# yawc.net
KiCad netlist of a schematic drawn in EAGLE
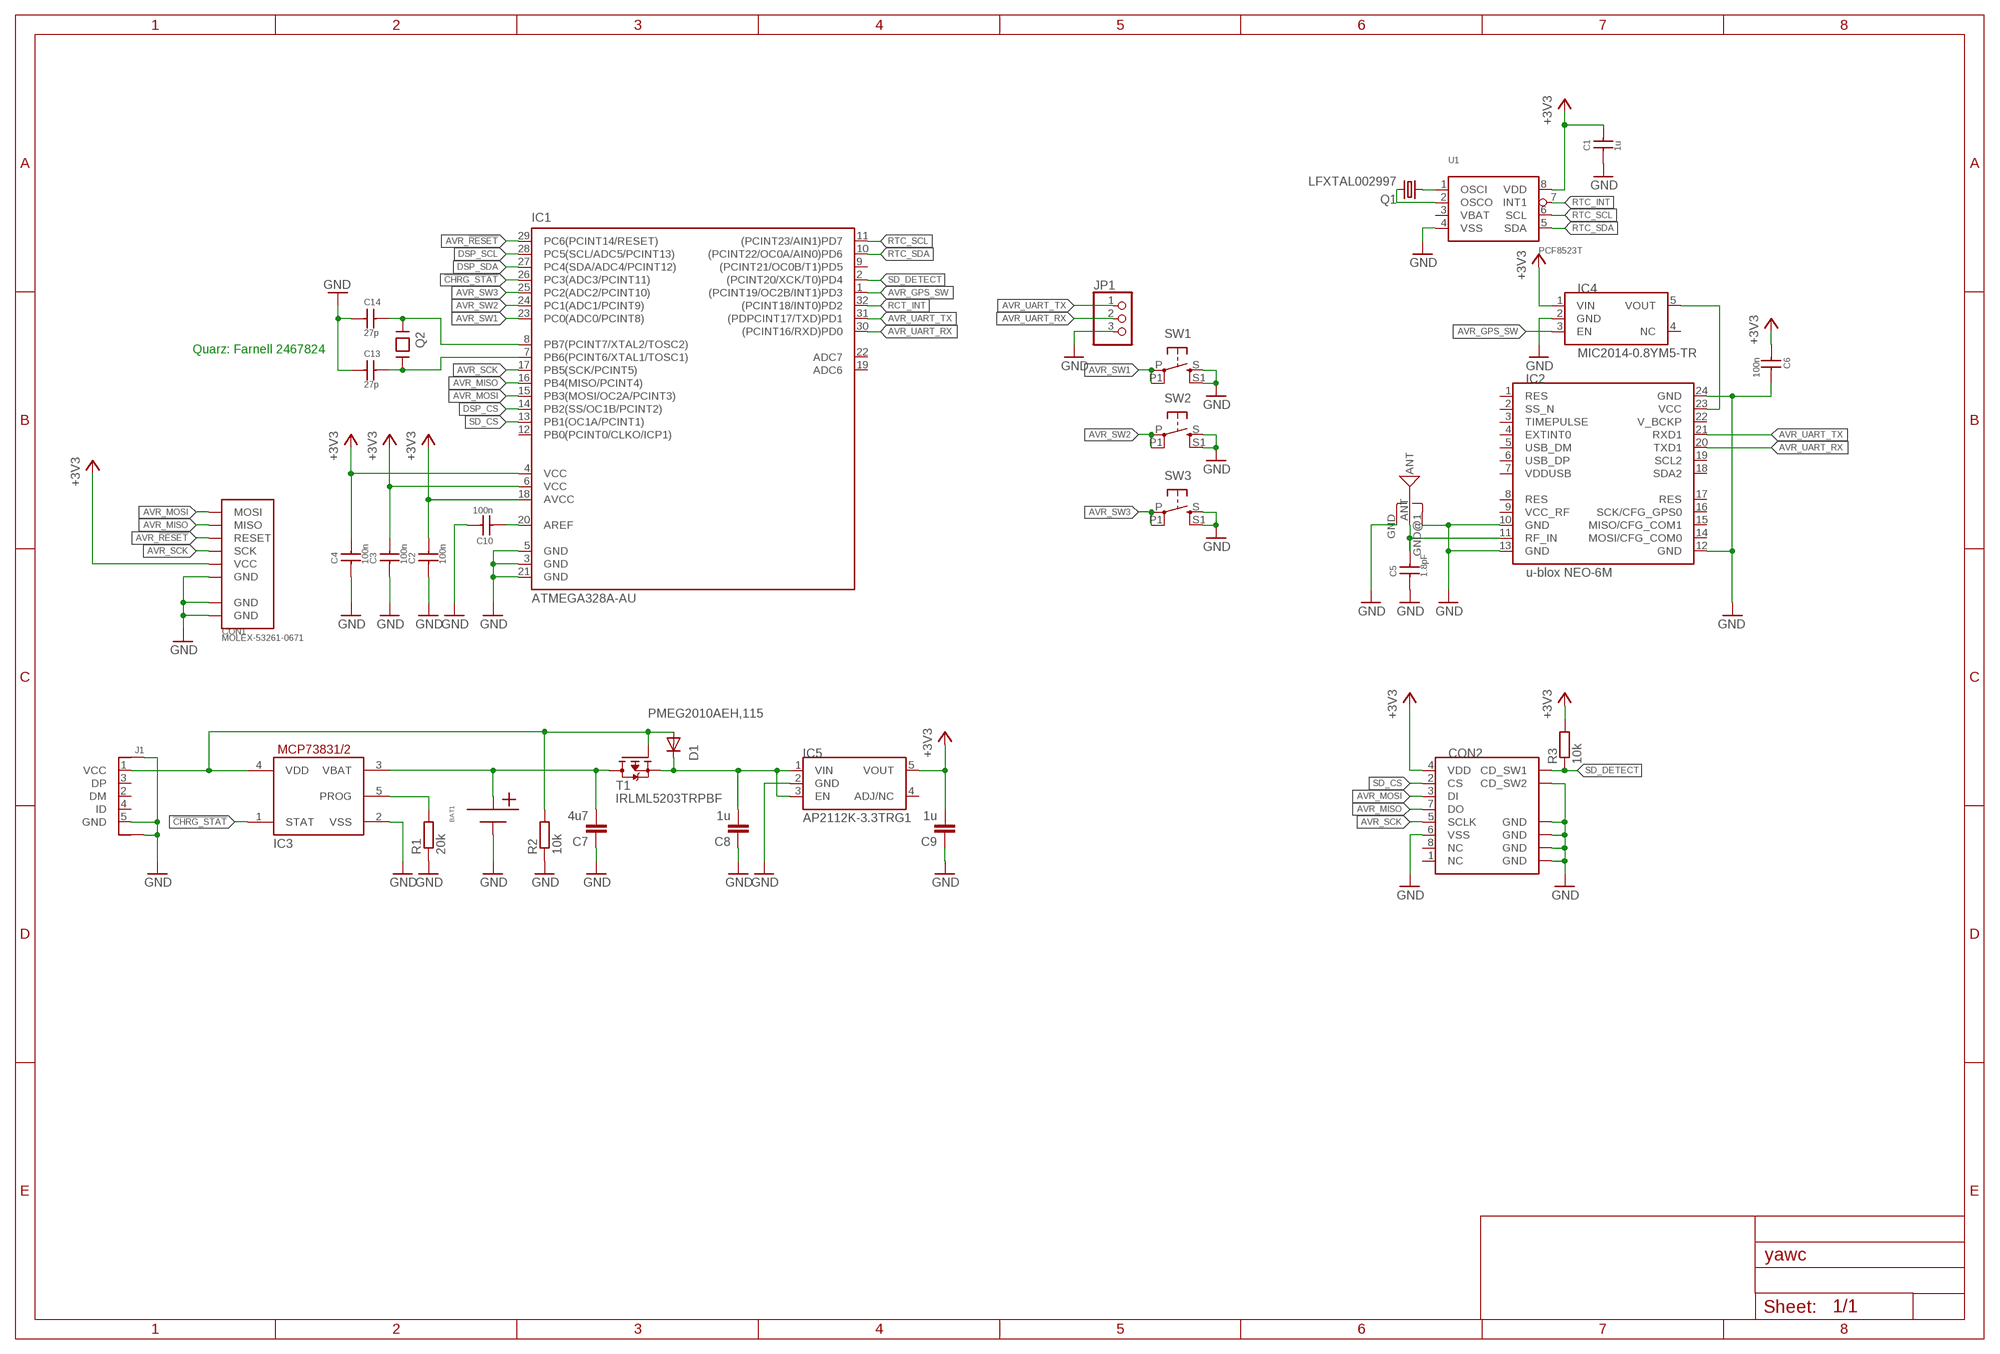
[diagram p0: schematic, sheet 1]

(export (version "E")
  (design (tool "Eeschema 10.0.6"))
  (components
    (comp (ref "BAT1")
      (value "LIPO_1S")
      (footprint "eagle-import:LIPO_1S_SOLDER_CON")
      (libsource (lib "eagle-import") (part "LIPO_1S"))
    )
    (comp (ref "C1")
      (value "1u")
      (footprint "eagle-import:C0603")
      (libsource (lib "eagle-import") (part "C_SMD0603"))
    )
    (comp (ref "C2")
      (value "100n")
      (footprint "eagle-import:C0603")
      (libsource (lib "eagle-import") (part "C_SMD0603"))
    )
    (comp (ref "C3")
      (value "100n")
      (footprint "eagle-import:C0603")
      (libsource (lib "eagle-import") (part "C_SMD0603"))
    )
    (comp (ref "C4")
      (value "100n")
      (footprint "eagle-import:C0603")
      (libsource (lib "eagle-import") (part "C_SMD0603"))
    )
    (comp (ref "C5")
      (value "1.8pF")
      (footprint "eagle-import:C0603")
      (libsource (lib "eagle-import") (part "C_SMD0603"))
    )
    (comp (ref "C6")
      (value "100n")
      (footprint "eagle-import:C0603")
      (libsource (lib "eagle-import") (part "C_SMD0603"))
    )
    (comp (ref "C7")
      (value "4u7")
      (footprint "eagle-import:C0805")
      (libsource (lib "eagle-import") (part "C-EUC0805"))
    )
    (comp (ref "C8")
      (value "1u")
      (footprint "eagle-import:C0805")
      (libsource (lib "eagle-import") (part "C-EUC0805"))
    )
    (comp (ref "C9")
      (value "1u")
      (footprint "eagle-import:C0805")
      (libsource (lib "eagle-import") (part "C-EUC0805"))
    )
    (comp (ref "C10")
      (value "100n")
      (footprint "eagle-import:C0603")
      (libsource (lib "eagle-import") (part "C_SMD0603"))
    )
    (comp (ref "C13")
      (value "27p")
      (footprint "eagle-import:C0603")
      (libsource (lib "eagle-import") (part "C_SMD0603"))
    )
    (comp (ref "C14")
      (value "27p")
      (footprint "eagle-import:C0603")
      (libsource (lib "eagle-import") (part "C_SMD0603"))
    )
    (comp (ref "CON1")
      (value "MOLEX-53261-0671")
      (footprint "eagle-import:MOLEX-53261-0671")
      (libsource (lib "eagle-import") (part "MOLEX-53261-0671"))
    )
    (comp (ref "CON2")
      (value "MICRO_SD_1140084168")
      (footprint "eagle-import:MICRO_SD_1140084168")
      (libsource (lib "eagle-import") (part "MICRO_SD_1140084168"))
    )
    (comp (ref "D1")
      (value "PMEG2010AEH,115")
      (footprint "eagle-import:SOD123")
      (libsource (lib "eagle-import") (part "PMEG2010AEH,115"))
    )
    (comp (ref "IC1")
      (value "ATMEGA328A-AU")
      (footprint "eagle-import:TQFP32")
      (libsource (lib "eagle-import") (part "ATMEGA48A-AU"))
    )
    (comp (ref "IC2")
      (value "u-blox NEO-6M")
      (footprint "eagle-import:NEO-6")
      (libsource (lib "eagle-import") (part "NEO-6M"))
    )
    (comp (ref "IC3")
      (value "MCP73831/OT")
      (footprint "eagle-import:SOT23-5L")
      (libsource (lib "eagle-import") (part "MCP73831/OT"))
    )
    (comp (ref "IC4")
      (value "MIC2014-0.8YM5-TR")
      (footprint "eagle-import:SOT-23-5")
      (libsource (lib "eagle-import") (part "MIC2014-0.8YM5-TR"))
    )
    (comp (ref "IC5")
      (value "AP2112K-3.3TRG1")
      (footprint "eagle-import:SOT-23-5")
      (libsource (lib "eagle-import") (part "AP2112K-3.3TRG1"))
    )
    (comp (ref "J1")
      (value "XM7D-0512")
      (footprint "eagle-import:XM7D-0512")
      (libsource (lib "eagle-import") (part "XM7D-0512"))
    )
    (comp (ref "JP1")
      (value "PINHD-1X3")
      (footprint "eagle-import:1X03")
      (libsource (lib "eagle-import") (part "PINHD-1X3"))
    )
    (comp (ref "Q1")
      (value "LFXTAL002997")
      (footprint "eagle-import:TC26H")
      (libsource (lib "eagle-import") (part "CRYSTALTC26H"))
    )
    (comp (ref "Q2")
      (value "16MHz")
      (footprint "eagle-import:CRYSTAL-ABRACON-ABM7-SMD")
      (libsource (lib "eagle-import") (part "CRYSTAL-ABRACON-ABM7-SMD"))
    )
    (comp (ref "R1")
      (value "20k")
      (footprint "eagle-import:R0603")
      (libsource (lib "eagle-import") (part "R-EU_R0603"))
    )
    (comp (ref "R2")
      (value "10k")
      (footprint "eagle-import:R0603")
      (libsource (lib "eagle-import") (part "R-EU_R0603"))
    )
    (comp (ref "R3")
      (value "10k")
      (footprint "eagle-import:R0603")
      (libsource (lib "eagle-import") (part "R-EU_R0603"))
    )
    (comp (ref "SW1")
      (value "ALPS_SKHHLNA010")
      (footprint "eagle-import:ALPS_SKHHLNA010")
      (libsource (lib "eagle-import") (part "ALPS_SKHHLNA010"))
    )
    (comp (ref "SW2")
      (value "ALPS_SKHHLNA010")
      (footprint "eagle-import:ALPS_SKHHLNA010")
      (libsource (lib "eagle-import") (part "ALPS_SKHHLNA010"))
    )
    (comp (ref "SW3")
      (value "ALPS_SKHHLNA010")
      (footprint "eagle-import:ALPS_SKHHLNA010")
      (libsource (lib "eagle-import") (part "ALPS_SKHHLNA010"))
    )
    (comp (ref "T1")
      (value "IRLML5203TRPBF")
      (footprint "eagle-import:SOT23")
      (libsource (lib "eagle-import") (part "IRLML5203TRPBF"))
    )
    (comp (ref "U$1")
      (value "ANT_W3011PULSE_1575MHZ")
      (footprint "eagle-import:ANT4MMX4.25MM")
      (libsource (lib "eagle-import") (part "ANT_W3011PULSE_1575MHZ"))
    )
    (comp (ref "U1")
      (value "PCF8523T")
      (footprint "eagle-import:SOT96-1")
      (libsource (lib "eagle-import") (part "PCF8523T"))
    )
  )
  (nets
    (net (code "1") (name "+3V3") (class "Default")
      (node (ref "C1") (pin "2") (pinfunction "P$2_2") (pintype "passive"))
      (node (ref "C2") (pin "2") (pinfunction "P$2_2") (pintype "passive"))
      (node (ref "C3") (pin "2") (pinfunction "P$2_2") (pintype "passive"))
      (node (ref "C4") (pin "2") (pinfunction "P$2_2") (pintype "passive"))
      (node (ref "C6") (pin "1") (pinfunction "P$1_1") (pintype "passive"))
      (node (ref "C9") (pin "2") (pinfunction "2_2") (pintype "passive"))
      (node (ref "CON1") (pin "5") (pinfunction "VCC_5") (pintype "bidirectional"))
      (node (ref "CON2") (pin "4") (pinfunction "VDD_4") (pintype "bidirectional"))
      (node (ref "IC1") (pin "18") (pinfunction "AVCC_18") (pintype "power_in"))
      (node (ref "IC1") (pin "4") (pinfunction "VCC_4") (pintype "power_in"))
      (node (ref "IC1") (pin "6") (pinfunction "VCC_6") (pintype "power_in"))
      (node (ref "IC4") (pin "1") (pinfunction "VIN_1") (pintype "bidirectional"))
      (node (ref "IC5") (pin "5") (pinfunction "VOUT_5") (pintype "bidirectional"))
      (node (ref "R3") (pin "2") (pinfunction "2_2") (pintype "passive"))
      (node (ref "U1") (pin "8") (pinfunction "VDD_8") (pintype "power_in"))
    )
    (net (code "2") (name "/AVR_~{RESET}") (class "Default")
      (node (ref "CON1") (pin "3") (pinfunction "RESET_3") (pintype "bidirectional"))
      (node (ref "IC1") (pin "29") (pinfunction "PC6(PCINT14/RESET)_29") (pintype "bidirectional"))
    )
    (net (code "3") (name "/VBAT") (class "Default")
      (node (ref "U1") (pin "3") (pinfunction "VBAT_3") (pintype "power_in"))
    )
    (net (code "4") (name "/~{CHRG_STAT}") (class "Default")
      (node (ref "IC1") (pin "26") (pinfunction "PC3(ADC3/PCINT11)_26") (pintype "bidirectional"))
      (node (ref "IC3") (pin "1") (pinfunction "STAT_1") (pintype "output"))
    )
    (net (code "5") (name "AVR_GPS_SW") (class "Default")
      (node (ref "IC1") (pin "1") (pinfunction "(PCINT19/OC2B/INT1)PD3_1") (pintype "bidirectional"))
      (node (ref "IC4") (pin "3") (pinfunction "EN_3") (pintype "bidirectional"))
    )
    (net (code "6") (name "AVR_MISO") (class "Default")
      (node (ref "CON1") (pin "2") (pinfunction "MISO_2") (pintype "bidirectional"))
      (node (ref "CON2") (pin "7") (pinfunction "DO_7") (pintype "bidirectional"))
      (node (ref "IC1") (pin "16") (pinfunction "PB4(MISO/PCINT4)_16") (pintype "bidirectional"))
    )
    (net (code "7") (name "AVR_MOSI") (class "Default")
      (node (ref "CON1") (pin "1") (pinfunction "MOSI_1") (pintype "bidirectional"))
      (node (ref "CON2") (pin "3") (pinfunction "DI_3") (pintype "bidirectional"))
      (node (ref "IC1") (pin "15") (pinfunction "PB3(MOSI/OC2A/PCINT3)_15") (pintype "bidirectional"))
    )
    (net (code "8") (name "AVR_SCK") (class "Default")
      (node (ref "CON1") (pin "4") (pinfunction "SCK_4") (pintype "bidirectional"))
      (node (ref "CON2") (pin "5") (pinfunction "SCLK_5") (pintype "bidirectional"))
      (node (ref "IC1") (pin "17") (pinfunction "PB5(SCK/PCINT5)_17") (pintype "bidirectional"))
    )
    (net (code "9") (name "AVR_SW1") (class "Default")
      (node (ref "IC1") (pin "23") (pinfunction "PC0(ADC0/PCINT8)_23") (pintype "bidirectional"))
      (node (ref "SW1") (pin "P") (pinfunction "P_P") (pintype "passive"))
      (node (ref "SW1") (pin "P1") (pinfunction "P1_P1") (pintype "passive"))
    )
    (net (code "10") (name "AVR_SW2") (class "Default")
      (node (ref "IC1") (pin "24") (pinfunction "PC1(ADC1/PCINT9)_24") (pintype "bidirectional"))
      (node (ref "SW2") (pin "P") (pinfunction "P_P") (pintype "passive"))
      (node (ref "SW2") (pin "P1") (pinfunction "P1_P1") (pintype "passive"))
    )
    (net (code "11") (name "AVR_SW3") (class "Default")
      (node (ref "IC1") (pin "25") (pinfunction "PC2(ADC2/PCINT10)_25") (pintype "bidirectional"))
      (node (ref "SW3") (pin "P") (pinfunction "P_P") (pintype "passive"))
      (node (ref "SW3") (pin "P1") (pinfunction "P1_P1") (pintype "passive"))
    )
    (net (code "12") (name "AVR_UART_RX") (class "Default")
      (node (ref "IC1") (pin "30") (pinfunction "(PCINT16/RXD)PD0_30") (pintype "bidirectional"))
      (node (ref "IC2") (pin "20") (pinfunction "TXD1_20") (pintype "bidirectional"))
      (node (ref "JP1") (pin "2") (pinfunction "2_2") (pintype "passive"))
    )
    (net (code "13") (name "AVR_UART_TX") (class "Default")
      (node (ref "IC1") (pin "31") (pinfunction "(PDPCINT17/TXD)PD1_31") (pintype "bidirectional"))
      (node (ref "IC2") (pin "21") (pinfunction "RXD1_21") (pintype "bidirectional"))
      (node (ref "JP1") (pin "1") (pinfunction "1_1") (pintype "passive"))
    )
    (net (code "14") (name "DSP_CS") (class "Default")
      (node (ref "IC1") (pin "14") (pinfunction "PB2(SS/OC1B/PCINT2)_14") (pintype "bidirectional"))
    )
    (net (code "15") (name "DSP_SCL") (class "Default")
      (node (ref "IC1") (pin "28") (pinfunction "PC5(SCL/ADC5/PCINT13)_28") (pintype "bidirectional"))
    )
    (net (code "16") (name "DSP_SDA") (class "Default")
      (node (ref "IC1") (pin "27") (pinfunction "PC4(SDA/ADC4/PCINT12)_27") (pintype "bidirectional"))
    )
    (net (code "17") (name "GND") (class "Default")
      (node (ref "BAT1") (pin "P$1") (pinfunction "+_P$1") (pintype "bidirectional"))
      (node (ref "C1") (pin "1") (pinfunction "P$1_1") (pintype "passive"))
      (node (ref "C10") (pin "2") (pinfunction "P$2_2") (pintype "passive"))
      (node (ref "C13") (pin "1") (pinfunction "P$1_1") (pintype "passive"))
      (node (ref "C14") (pin "1") (pinfunction "P$1_1") (pintype "passive"))
      (node (ref "C2") (pin "1") (pinfunction "P$1_1") (pintype "passive"))
      (node (ref "C3") (pin "1") (pinfunction "P$1_1") (pintype "passive"))
      (node (ref "C4") (pin "1") (pinfunction "P$1_1") (pintype "passive"))
      (node (ref "C5") (pin "1") (pinfunction "P$1_1") (pintype "passive"))
      (node (ref "C6") (pin "2") (pinfunction "P$2_2") (pintype "passive"))
      (node (ref "C7") (pin "1") (pinfunction "1_1") (pintype "passive"))
      (node (ref "C8") (pin "1") (pinfunction "1_1") (pintype "passive"))
      (node (ref "C9") (pin "1") (pinfunction "1_1") (pintype "passive"))
      (node (ref "CON1") (pin "6") (pinfunction "GND_6") (pintype "bidirectional"))
      (node (ref "CON1") (pin "GND@1") (pinfunction "GND_GND@1") (pintype "power_in"))
      (node (ref "CON1") (pin "GND@2") (pinfunction "GND_GND@2") (pintype "power_in"))
      (node (ref "CON2") (pin "6") (pinfunction "VSS_6") (pintype "bidirectional"))
      (node (ref "CON2") (pin "CD@2") (pinfunction "CD_SW2_CD@2") (pintype "bidirectional"))
      (node (ref "CON2") (pin "GND@1") (pinfunction "GND_GND@1") (pintype "bidirectional"))
      (node (ref "CON2") (pin "GND@2") (pinfunction "GND_GND@2") (pintype "bidirectional"))
      (node (ref "CON2") (pin "GND@3") (pinfunction "GND_GND@3") (pintype "bidirectional"))
      (node (ref "CON2") (pin "GND@4") (pinfunction "GND_GND@4") (pintype "bidirectional"))
      (node (ref "IC1") (pin "21") (pinfunction "GND_21") (pintype "power_in"))
      (node (ref "IC1") (pin "3") (pinfunction "GND_3") (pintype "power_in"))
      (node (ref "IC1") (pin "5") (pinfunction "GND_5") (pintype "power_in"))
      (node (ref "IC2") (pin "10") (pinfunction "GND_10") (pintype "bidirectional"))
      (node (ref "IC2") (pin "12") (pinfunction "GND_12") (pintype "bidirectional"))
      (node (ref "IC2") (pin "13") (pinfunction "GND_13") (pintype "bidirectional"))
      (node (ref "IC2") (pin "24") (pinfunction "GND_24") (pintype "bidirectional"))
      (node (ref "IC3") (pin "2") (pinfunction "VSS_2") (pintype "power_in"))
      (node (ref "IC4") (pin "2") (pinfunction "GND_2") (pintype "bidirectional"))
      (node (ref "IC5") (pin "2") (pinfunction "GND_2") (pintype "bidirectional"))
      (node (ref "J1") (pin "5") (pinfunction "GND_5") (pintype "bidirectional"))
      (node (ref "J1") (pin "P$8") (pinfunction "GND_P$8") (pintype "bidirectional"))
      (node (ref "J1") (pin "P$9") (pinfunction "GND_P$9") (pintype "bidirectional"))
      (node (ref "JP1") (pin "3") (pinfunction "3_3") (pintype "passive"))
      (node (ref "R1") (pin "1") (pinfunction "1_1") (pintype "passive"))
      (node (ref "R2") (pin "1") (pinfunction "1_1") (pintype "passive"))
      (node (ref "SW1") (pin "S") (pinfunction "S_S") (pintype "passive"))
      (node (ref "SW1") (pin "S1") (pinfunction "S1_S1") (pintype "passive"))
      (node (ref "SW2") (pin "S") (pinfunction "S_S") (pintype "passive"))
      (node (ref "SW2") (pin "S1") (pinfunction "S1_S1") (pintype "passive"))
      (node (ref "SW3") (pin "S") (pinfunction "S_S") (pintype "passive"))
      (node (ref "SW3") (pin "S1") (pinfunction "S1_S1") (pintype "passive"))
      (node (ref "U$1") (pin "GND") (pinfunction "GND_GND") (pintype "bidirectional"))
      (node (ref "U$1") (pin "GND@1") (pinfunction "GND_GND@1") (pintype "bidirectional"))
      (node (ref "U1") (pin "4") (pinfunction "VSS_4") (pintype "power_in"))
    )
    (net (code "18") (name "Net-(BAT1--)") (class "Default")
      (node (ref "BAT1") (pin "P$2") (pinfunction "-_P$2") (pintype "bidirectional"))
      (node (ref "C7") (pin "2") (pinfunction "2_2") (pintype "passive"))
      (node (ref "IC3") (pin "3") (pinfunction "VBAT_3") (pintype "bidirectional"))
      (node (ref "T1") (pin "3") (pinfunction "D_3") (pintype "passive"))
    )
    (net (code "19") (name "Net-(C5-P$2)") (class "Default")
      (node (ref "C5") (pin "2") (pinfunction "P$2_2") (pintype "passive"))
      (node (ref "IC2") (pin "11") (pinfunction "RF_IN_11") (pintype "bidirectional"))
      (node (ref "U$1") (pin "ANT") (pinfunction "ANT_ANT") (pintype "bidirectional"))
    )
    (net (code "20") (name "Net-(C10-P$1)") (class "Default")
      (node (ref "C10") (pin "1") (pinfunction "P$1_1") (pintype "passive"))
      (node (ref "IC1") (pin "20") (pinfunction "AREF_20") (pintype "power_in"))
    )
    (net (code "21") (name "Net-(C13-P$2)") (class "Default")
      (node (ref "C13") (pin "2") (pinfunction "P$2_2") (pintype "passive"))
      (node (ref "IC1") (pin "7") (pinfunction "PB6(PCINT6/XTAL1/TOSC1)_7") (pintype "bidirectional"))
      (node (ref "Q2") (pin "P$2") (pinfunction "P$2_P$2") (pintype "bidirectional"))
    )
    (net (code "22") (name "Net-(C14-P$2)") (class "Default")
      (node (ref "C14") (pin "2") (pinfunction "P$2_2") (pintype "passive"))
      (node (ref "IC1") (pin "8") (pinfunction "PB7(PCINT7/XTAL2/TOSC2)_8") (pintype "bidirectional"))
      (node (ref "Q2") (pin "P$1") (pinfunction "P$1_P$1") (pintype "bidirectional"))
    )
    (net (code "23") (name "Net-(IC2-VCC)") (class "Default")
      (node (ref "IC2") (pin "23") (pinfunction "VCC_23") (pintype "bidirectional"))
      (node (ref "IC4") (pin "5") (pinfunction "VOUT_5") (pintype "bidirectional"))
    )
    (net (code "24") (name "Net-(IC3-PROG)") (class "Default")
      (node (ref "IC3") (pin "5") (pinfunction "PROG_5") (pintype "input"))
      (node (ref "R1") (pin "2") (pinfunction "2_2") (pintype "passive"))
    )
    (net (code "25") (name "Net-(IC3-VDD)") (class "Default")
      (node (ref "D1") (pin "A") (pinfunction "A_A") (pintype "passive"))
      (node (ref "IC3") (pin "4") (pinfunction "VDD_4") (pintype "power_in"))
      (node (ref "J1") (pin "1") (pinfunction "VCC_1") (pintype "bidirectional"))
      (node (ref "R2") (pin "2") (pinfunction "2_2") (pintype "passive"))
      (node (ref "T1") (pin "1") (pinfunction "G_1") (pintype "passive"))
    )
    (net (code "26") (name "Net-(IC5-EN)") (class "Default")
      (node (ref "C8") (pin "2") (pinfunction "2_2") (pintype "passive"))
      (node (ref "D1") (pin "C") (pinfunction "C_C") (pintype "passive"))
      (node (ref "IC5") (pin "1") (pinfunction "VIN_1") (pintype "bidirectional"))
      (node (ref "IC5") (pin "3") (pinfunction "EN_3") (pintype "bidirectional"))
      (node (ref "T1") (pin "2") (pinfunction "S_2") (pintype "passive"))
    )
    (net (code "27") (name "Net-(U1-OSCI)") (class "Default")
      (node (ref "Q1") (pin "1") (pinfunction "1_1") (pintype "passive"))
      (node (ref "U1") (pin "1") (pinfunction "OSCI_1") (pintype "passive"))
    )
    (net (code "28") (name "Net-(U1-OSCO)") (class "Default")
      (node (ref "Q1") (pin "2") (pinfunction "2_2") (pintype "passive"))
      (node (ref "U1") (pin "2") (pinfunction "OSCO_2") (pintype "passive"))
    )
    (net (code "29") (name "RCT_INT") (class "Default")
      (node (ref "IC1") (pin "32") (pinfunction "(PCINT18/INT0)PD2_32") (pintype "bidirectional"))
    )
    (net (code "30") (name "RTC_INT") (class "Default")
      (node (ref "U1") (pin "7") (pinfunction "INT1_7") (pintype "output"))
    )
    (net (code "31") (name "RTC_SCL") (class "Default")
      (node (ref "IC1") (pin "11") (pinfunction "(PCINT23/AIN1)PD7_11") (pintype "bidirectional"))
      (node (ref "U1") (pin "6") (pinfunction "SCL_6") (pintype "input"))
    )
    (net (code "32") (name "RTC_SDA") (class "Default")
      (node (ref "IC1") (pin "10") (pinfunction "(PCINT22/OC0A/AIN0)PD6_10") (pintype "bidirectional"))
      (node (ref "U1") (pin "5") (pinfunction "SDA_5") (pintype "bidirectional"))
    )
    (net (code "33") (name "SD_CS") (class "Default")
      (node (ref "CON2") (pin "2") (pinfunction "CS_2") (pintype "bidirectional"))
      (node (ref "IC1") (pin "13") (pinfunction "PB1(OC1A/PCINT1)_13") (pintype "bidirectional"))
    )
    (net (code "34") (name "SD_DETECT") (class "Default")
      (node (ref "CON2") (pin "CD@1") (pinfunction "CD_SW1_CD@1") (pintype "bidirectional"))
      (node (ref "IC1") (pin "2") (pinfunction "(PCINT20/XCK/T0)PD4_2") (pintype "bidirectional"))
      (node (ref "R3") (pin "1") (pinfunction "1_1") (pintype "passive"))
    )
    (net (code "35") (name "unconnected-(CON2-NC-Pad1)") (class "Default")
      (node (ref "CON2") (pin "1") (pinfunction "NC_1") (pintype "bidirectional"))
    )
    (net (code "36") (name "unconnected-(CON2-NC-Pad8)") (class "Default")
      (node (ref "CON2") (pin "8") (pinfunction "NC_8") (pintype "bidirectional"))
    )
    (net (code "37") (name "unconnected-(IC1-(PCINT21{slash}OC0B{slash}T1)PD5-Pad9)") (class "Default")
      (node (ref "IC1") (pin "9") (pinfunction "(PCINT21/OC0B/T1)PD5_9") (pintype "bidirectional"))
    )
    (net (code "38") (name "unconnected-(IC1-ADC6-Pad19)") (class "Default")
      (node (ref "IC1") (pin "19") (pinfunction "ADC6_19") (pintype "bidirectional"))
    )
    (net (code "39") (name "unconnected-(IC1-ADC7-Pad22)") (class "Default")
      (node (ref "IC1") (pin "22") (pinfunction "ADC7_22") (pintype "bidirectional"))
    )
    (net (code "40") (name "unconnected-(IC1-PB0(PCINT0{slash}CLKO{slash}ICP1)-Pad12)") (class "Default")
      (node (ref "IC1") (pin "12") (pinfunction "PB0(PCINT0/CLKO/ICP1)_12") (pintype "bidirectional"))
    )
    (net (code "41") (name "unconnected-(IC2-EXTINT0-Pad4)") (class "Default")
      (node (ref "IC2") (pin "4") (pinfunction "EXTINT0_4") (pintype "bidirectional"))
    )
    (net (code "42") (name "unconnected-(IC2-MISO{slash}CFG_COM1-Pad15)") (class "Default")
      (node (ref "IC2") (pin "15") (pinfunction "MISO/CFG_COM1_15") (pintype "bidirectional"))
    )
    (net (code "43") (name "unconnected-(IC2-MOSI{slash}CFG_COM0-Pad14)") (class "Default")
      (node (ref "IC2") (pin "14") (pinfunction "MOSI/CFG_COM0_14") (pintype "bidirectional"))
    )
    (net (code "44") (name "unconnected-(IC2-RES-Pad1)") (class "Default")
      (node (ref "IC2") (pin "1") (pinfunction "RES_1") (pintype "bidirectional"))
    )
    (net (code "45") (name "unconnected-(IC2-RES-Pad8)") (class "Default")
      (node (ref "IC2") (pin "8") (pinfunction "RES_8") (pintype "bidirectional"))
    )
    (net (code "46") (name "unconnected-(IC2-RES-Pad17)") (class "Default")
      (node (ref "IC2") (pin "17") (pinfunction "RES_17") (pintype "bidirectional"))
    )
    (net (code "47") (name "unconnected-(IC2-SCK{slash}CFG_GPS0-Pad16)") (class "Default")
      (node (ref "IC2") (pin "16") (pinfunction "SCK/CFG_GPS0_16") (pintype "bidirectional"))
    )
    (net (code "48") (name "unconnected-(IC2-SCL2-Pad19)") (class "Default")
      (node (ref "IC2") (pin "19") (pinfunction "SCL2_19") (pintype "bidirectional"))
    )
    (net (code "49") (name "unconnected-(IC2-SDA2-Pad18)") (class "Default")
      (node (ref "IC2") (pin "18") (pinfunction "SDA2_18") (pintype "bidirectional"))
    )
    (net (code "50") (name "unconnected-(IC2-SS_N-Pad2)") (class "Default")
      (node (ref "IC2") (pin "2") (pinfunction "SS_N_2") (pintype "bidirectional"))
    )
    (net (code "51") (name "unconnected-(IC2-TIMEPULSE-Pad3)") (class "Default")
      (node (ref "IC2") (pin "3") (pinfunction "TIMEPULSE_3") (pintype "bidirectional"))
    )
    (net (code "52") (name "unconnected-(IC2-USB_DM-Pad5)") (class "Default")
      (node (ref "IC2") (pin "5") (pinfunction "USB_DM_5") (pintype "bidirectional"))
    )
    (net (code "53") (name "unconnected-(IC2-USB_DP-Pad6)") (class "Default")
      (node (ref "IC2") (pin "6") (pinfunction "USB_DP_6") (pintype "bidirectional"))
    )
    (net (code "54") (name "unconnected-(IC2-VCC_RF-Pad9)") (class "Default")
      (node (ref "IC2") (pin "9") (pinfunction "VCC_RF_9") (pintype "bidirectional"))
    )
    (net (code "55") (name "unconnected-(IC2-VDDUSB-Pad7)") (class "Default")
      (node (ref "IC2") (pin "7") (pinfunction "VDDUSB_7") (pintype "bidirectional"))
    )
    (net (code "56") (name "unconnected-(IC2-V_BCKP-Pad22)") (class "Default")
      (node (ref "IC2") (pin "22") (pinfunction "V_BCKP_22") (pintype "bidirectional"))
    )
    (net (code "57") (name "unconnected-(IC4-NC-Pad4)") (class "Default")
      (node (ref "IC4") (pin "4") (pinfunction "NC_4") (pintype "bidirectional"))
    )
    (net (code "58") (name "unconnected-(IC5-ADJ{slash}NC-Pad4)") (class "Default")
      (node (ref "IC5") (pin "4") (pinfunction "ADJ/NC_4") (pintype "bidirectional"))
    )
    (net (code "59") (name "unconnected-(J1-DM-Pad2)") (class "Default")
      (node (ref "J1") (pin "2") (pinfunction "DM_2") (pintype "bidirectional"))
    )
    (net (code "60") (name "unconnected-(J1-DP-Pad3)") (class "Default")
      (node (ref "J1") (pin "3") (pinfunction "DP_3") (pintype "bidirectional"))
    )
    (net (code "61") (name "unconnected-(J1-ID-Pad4)") (class "Default")
      (node (ref "J1") (pin "4") (pinfunction "ID_4") (pintype "bidirectional"))
    )
  )
)
